# SOM_IO2.net
KiCad netlist of a schematic drawn in Altium Designer
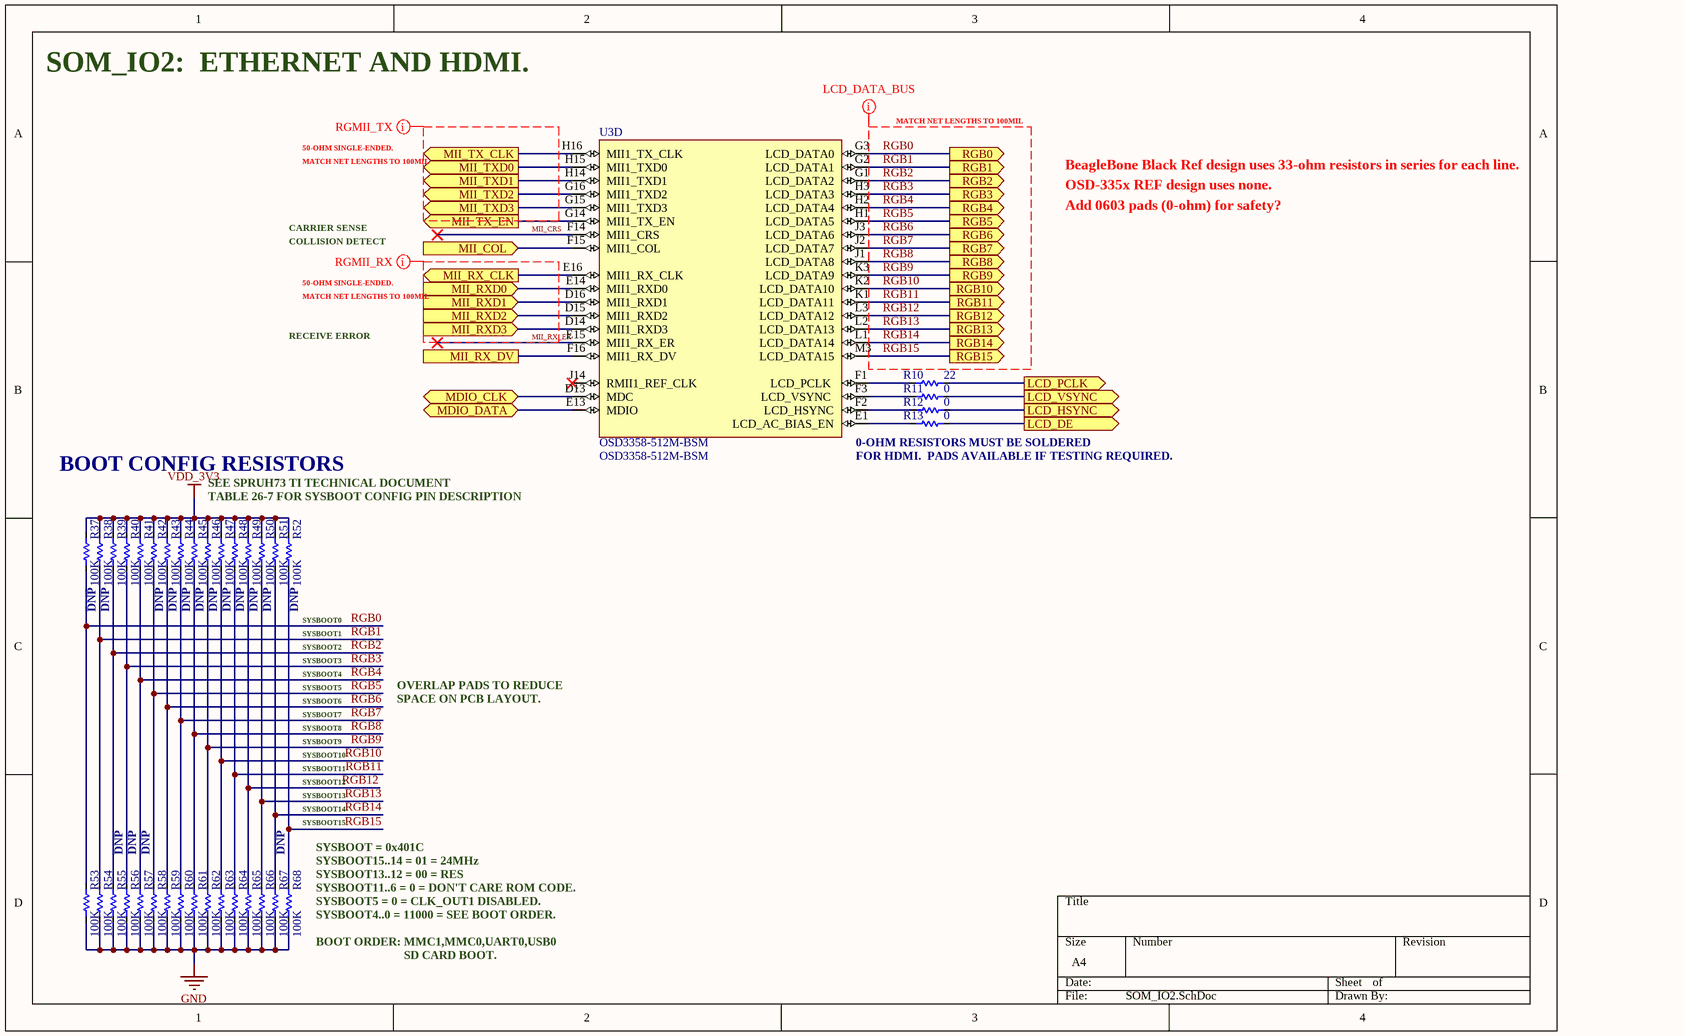
[diagram p0: SOM_IO2.SchDoc]

(export (version "E")
  (design (tool "Eeschema 10.0.6"))
  (components
    (comp (ref "R10")
      (value "22")
      (footprint "RES_0603")
      (description "RES SMD 22 OHM 5% 1/10W 0603")
      (fields (field (name "TOLERANCE") "5%") (field (name "MANUFACTURER") "Yageo"))
      (libsource (lib "OSD335-X_Devboard") (part "RC0603JR-0722RL"))
    )
    (comp (ref "R11")
      (value "0")
      (footprint "RES_0603")
      (description "RES SMD 0 OHM JUMPER 1/10W 0603")
      (fields (field (name "MANUFACTURER") "Yageo") (field (name "MANUFACTURER PART NO.") "RC0603JR-070RL"))
      (libsource (lib "OSD335-X_Devboard") (part "RC0603JR-070RL"))
    )
    (comp (ref "R12")
      (value "0")
      (footprint "RES_0603")
      (description "RES SMD 0 OHM JUMPER 1/10W 0603")
      (fields (field (name "MANUFACTURER") "Yageo") (field (name "MANUFACTURER PART NO.") "RC0603JR-070RL"))
      (libsource (lib "OSD335-X_Devboard") (part "RC0603JR-070RL"))
    )
    (comp (ref "R13")
      (value "0")
      (footprint "RES_0603")
      (description "RES SMD 0 OHM JUMPER 1/10W 0603")
      (fields (field (name "MANUFACTURER") "Yageo") (field (name "MANUFACTURER PART NO.") "RC0603JR-070RL"))
      (libsource (lib "OSD335-X_Devboard") (part "RC0603JR-070RL"))
    )
    (comp (ref "R37")
      (value "100K")
      (footprint "RES_0402")
      (description "RES SMD 100K OHM 1% 1/16W 0402")
      (fields (field (name "TOLERANCE") "1%") (field (name "MANUFACTURER") "Yageo"))
      (libsource (lib "OSD335-X_Devboard") (part "RC0402FR-07100KL"))
    )
    (comp (ref "R38")
      (value "100K")
      (footprint "RES_0402")
      (description "RES SMD 100K OHM 1% 1/16W 0402")
      (fields (field (name "TOLERANCE") "1%") (field (name "MANUFACTURER") "Yageo"))
      (libsource (lib "OSD335-X_Devboard") (part "RC0402FR-07100KL"))
    )
    (comp (ref "R39")
      (value "100K")
      (footprint "RES_0402")
      (description "RES SMD 100K OHM 1% 1/16W 0402")
      (fields (field (name "TOLERANCE") "1%") (field (name "MANUFACTURER") "Yageo"))
      (libsource (lib "OSD335-X_Devboard") (part "RC0402FR-07100KL"))
    )
    (comp (ref "R40")
      (value "100K")
      (footprint "RES_0402")
      (description "RES SMD 100K OHM 1% 1/16W 0402")
      (fields (field (name "TOLERANCE") "1%") (field (name "MANUFACTURER") "Yageo"))
      (libsource (lib "OSD335-X_Devboard") (part "RC0402FR-07100KL"))
    )
    (comp (ref "R41")
      (value "100K")
      (footprint "RES_0402")
      (description "RES SMD 100K OHM 1% 1/16W 0402")
      (fields (field (name "TOLERANCE") "1%") (field (name "MANUFACTURER") "Yageo"))
      (libsource (lib "OSD335-X_Devboard") (part "RC0402FR-07100KL"))
    )
    (comp (ref "R42")
      (value "100K")
      (footprint "RES_0402")
      (description "RES SMD 100K OHM 1% 1/16W 0402")
      (fields (field (name "TOLERANCE") "1%") (field (name "MANUFACTURER") "Yageo"))
      (libsource (lib "OSD335-X_Devboard") (part "RC0402FR-07100KL"))
    )
    (comp (ref "R43")
      (value "100K")
      (footprint "RES_0402")
      (description "RES SMD 100K OHM 1% 1/16W 0402")
      (fields (field (name "TOLERANCE") "1%") (field (name "MANUFACTURER") "Yageo"))
      (libsource (lib "OSD335-X_Devboard") (part "RC0402FR-07100KL"))
    )
    (comp (ref "R44")
      (value "100K")
      (footprint "RES_0402")
      (description "RES SMD 100K OHM 1% 1/16W 0402")
      (fields (field (name "TOLERANCE") "1%") (field (name "MANUFACTURER") "Yageo"))
      (libsource (lib "OSD335-X_Devboard") (part "RC0402FR-07100KL"))
    )
    (comp (ref "R45")
      (value "100K")
      (footprint "RES_0402")
      (description "RES SMD 100K OHM 1% 1/16W 0402")
      (fields (field (name "TOLERANCE") "1%") (field (name "MANUFACTURER") "Yageo"))
      (libsource (lib "OSD335-X_Devboard") (part "RC0402FR-07100KL"))
    )
    (comp (ref "R46")
      (value "100K")
      (footprint "RES_0402")
      (description "RES SMD 100K OHM 1% 1/16W 0402")
      (fields (field (name "TOLERANCE") "1%") (field (name "MANUFACTURER") "Yageo"))
      (libsource (lib "OSD335-X_Devboard") (part "RC0402FR-07100KL"))
    )
    (comp (ref "R47")
      (value "100K")
      (footprint "RES_0402")
      (description "RES SMD 100K OHM 1% 1/16W 0402")
      (fields (field (name "TOLERANCE") "1%") (field (name "MANUFACTURER") "Yageo"))
      (libsource (lib "OSD335-X_Devboard") (part "RC0402FR-07100KL"))
    )
    (comp (ref "R48")
      (value "100K")
      (footprint "RES_0402")
      (description "RES SMD 100K OHM 1% 1/16W 0402")
      (fields (field (name "TOLERANCE") "1%") (field (name "MANUFACTURER") "Yageo"))
      (libsource (lib "OSD335-X_Devboard") (part "RC0402FR-07100KL"))
    )
    (comp (ref "R49")
      (value "100K")
      (footprint "RES_0402")
      (description "RES SMD 100K OHM 1% 1/16W 0402")
      (fields (field (name "TOLERANCE") "1%") (field (name "MANUFACTURER") "Yageo"))
      (libsource (lib "OSD335-X_Devboard") (part "RC0402FR-07100KL"))
    )
    (comp (ref "R50")
      (value "100K")
      (footprint "RES_0402")
      (description "RES SMD 100K OHM 1% 1/16W 0402")
      (fields (field (name "TOLERANCE") "1%") (field (name "MANUFACTURER") "Yageo"))
      (libsource (lib "OSD335-X_Devboard") (part "RC0402FR-07100KL"))
    )
    (comp (ref "R51")
      (value "100K")
      (footprint "RES_0402")
      (description "RES SMD 100K OHM 1% 1/16W 0402")
      (fields (field (name "TOLERANCE") "1%") (field (name "MANUFACTURER") "Yageo"))
      (libsource (lib "OSD335-X_Devboard") (part "RC0402FR-07100KL"))
    )
    (comp (ref "R52")
      (value "100K")
      (footprint "RES_0402")
      (description "RES SMD 100K OHM 1% 1/16W 0402")
      (fields (field (name "TOLERANCE") "1%") (field (name "MANUFACTURER") "Yageo"))
      (libsource (lib "OSD335-X_Devboard") (part "RC0402FR-07100KL"))
    )
    (comp (ref "R53")
      (value "100K")
      (footprint "RES_0402")
      (description "RES SMD 100K OHM 1% 1/16W 0402")
      (fields (field (name "TOLERANCE") "1%") (field (name "MANUFACTURER") "Yageo"))
      (libsource (lib "OSD335-X_Devboard") (part "RC0402FR-07100KL"))
    )
    (comp (ref "R54")
      (value "100K")
      (footprint "RES_0402")
      (description "RES SMD 100K OHM 1% 1/16W 0402")
      (fields (field (name "TOLERANCE") "1%") (field (name "MANUFACTURER") "Yageo"))
      (libsource (lib "OSD335-X_Devboard") (part "RC0402FR-07100KL"))
    )
    (comp (ref "R55")
      (value "100K")
      (footprint "RES_0402")
      (description "RES SMD 100K OHM 1% 1/16W 0402")
      (fields (field (name "TOLERANCE") "1%") (field (name "MANUFACTURER") "Yageo"))
      (libsource (lib "OSD335-X_Devboard") (part "RC0402FR-07100KL"))
    )
    (comp (ref "R56")
      (value "100K")
      (footprint "RES_0402")
      (description "RES SMD 100K OHM 1% 1/16W 0402")
      (fields (field (name "TOLERANCE") "1%") (field (name "MANUFACTURER") "Yageo"))
      (libsource (lib "OSD335-X_Devboard") (part "RC0402FR-07100KL"))
    )
    (comp (ref "R57")
      (value "100K")
      (footprint "RES_0402")
      (description "RES SMD 100K OHM 1% 1/16W 0402")
      (fields (field (name "TOLERANCE") "1%") (field (name "MANUFACTURER") "Yageo"))
      (libsource (lib "OSD335-X_Devboard") (part "RC0402FR-07100KL"))
    )
    (comp (ref "R58")
      (value "100K")
      (footprint "RES_0402")
      (description "RES SMD 100K OHM 1% 1/16W 0402")
      (fields (field (name "TOLERANCE") "1%") (field (name "MANUFACTURER") "Yageo"))
      (libsource (lib "OSD335-X_Devboard") (part "RC0402FR-07100KL"))
    )
    (comp (ref "R59")
      (value "100K")
      (footprint "RES_0402")
      (description "RES SMD 100K OHM 1% 1/16W 0402")
      (fields (field (name "TOLERANCE") "1%") (field (name "MANUFACTURER") "Yageo"))
      (libsource (lib "OSD335-X_Devboard") (part "RC0402FR-07100KL"))
    )
    (comp (ref "R60")
      (value "100K")
      (footprint "RES_0402")
      (description "RES SMD 100K OHM 1% 1/16W 0402")
      (fields (field (name "TOLERANCE") "1%") (field (name "MANUFACTURER") "Yageo"))
      (libsource (lib "OSD335-X_Devboard") (part "RC0402FR-07100KL"))
    )
    (comp (ref "R61")
      (value "100K")
      (footprint "RES_0402")
      (description "RES SMD 100K OHM 1% 1/16W 0402")
      (fields (field (name "TOLERANCE") "1%") (field (name "MANUFACTURER") "Yageo"))
      (libsource (lib "OSD335-X_Devboard") (part "RC0402FR-07100KL"))
    )
    (comp (ref "R62")
      (value "100K")
      (footprint "RES_0402")
      (description "RES SMD 100K OHM 1% 1/16W 0402")
      (fields (field (name "TOLERANCE") "1%") (field (name "MANUFACTURER") "Yageo"))
      (libsource (lib "OSD335-X_Devboard") (part "RC0402FR-07100KL"))
    )
    (comp (ref "R63")
      (value "100K")
      (footprint "RES_0402")
      (description "RES SMD 100K OHM 1% 1/16W 0402")
      (fields (field (name "TOLERANCE") "1%") (field (name "MANUFACTURER") "Yageo"))
      (libsource (lib "OSD335-X_Devboard") (part "RC0402FR-07100KL"))
    )
    (comp (ref "R64")
      (value "100K")
      (footprint "RES_0402")
      (description "RES SMD 100K OHM 1% 1/16W 0402")
      (fields (field (name "TOLERANCE") "1%") (field (name "MANUFACTURER") "Yageo"))
      (libsource (lib "OSD335-X_Devboard") (part "RC0402FR-07100KL"))
    )
    (comp (ref "R65")
      (value "100K")
      (footprint "RES_0402")
      (description "RES SMD 100K OHM 1% 1/16W 0402")
      (fields (field (name "TOLERANCE") "1%") (field (name "MANUFACTURER") "Yageo"))
      (libsource (lib "OSD335-X_Devboard") (part "RC0402FR-07100KL"))
    )
    (comp (ref "R66")
      (value "100K")
      (footprint "RES_0402")
      (description "RES SMD 100K OHM 1% 1/16W 0402")
      (fields (field (name "TOLERANCE") "1%") (field (name "MANUFACTURER") "Yageo"))
      (libsource (lib "OSD335-X_Devboard") (part "RC0402FR-07100KL"))
    )
    (comp (ref "R67")
      (value "100K")
      (footprint "RES_0402")
      (description "RES SMD 100K OHM 1% 1/16W 0402")
      (fields (field (name "TOLERANCE") "1%") (field (name "MANUFACTURER") "Yageo"))
      (libsource (lib "OSD335-X_Devboard") (part "RC0402FR-07100KL"))
    )
    (comp (ref "R68")
      (value "100K")
      (footprint "RES_0402")
      (description "RES SMD 100K OHM 1% 1/16W 0402")
      (fields (field (name "TOLERANCE") "1%") (field (name "MANUFACTURER") "Yageo"))
      (libsource (lib "OSD335-X_Devboard") (part "RC0402FR-07100KL"))
    )
    (comp (ref "U3")
      (value "OSD3358-512M-BSM")
      (footprint "BGA256C127P16X16_2100X2100X308")
      (description "OSD3358-512M-BSM , 256-FBGA, 21mmx21mmx3mm")
      (fields (field (name "MANUFACTURER") "Octavo Systems") (field (name "PARTNUMBER") "OSD3358-512M-BSM"))
      (libsource (lib "OSD335-X_Devboard") (part "SOM-OSD3358-512M-BSM"))
    )
  )
  (nets
    (net (code "1") (name "/LCD_DE") (class "Default")
      (node (ref "R13") (pin "2") (pinfunction "2_2") (pintype "passive"))
    )
    (net (code "2") (name "/LCD_HSYNC") (class "Default")
      (node (ref "R12") (pin "2") (pinfunction "2_2") (pintype "passive"))
    )
    (net (code "3") (name "/LCD_PCLK") (class "Default")
      (node (ref "R10") (pin "2") (pinfunction "2_2") (pintype "passive"))
    )
    (net (code "4") (name "/LCD_VSYNC") (class "Default")
      (node (ref "R11") (pin "2") (pinfunction "2_2") (pintype "passive"))
    )
    (net (code "5") (name "/MDIO_CLK") (class "Default")
      (node (ref "U3") (pin "D13") (pinfunction "MDC_D13") (pintype "bidirectional"))
    )
    (net (code "6") (name "/MDIO_DATA") (class "Default")
      (node (ref "U3") (pin "E13") (pinfunction "MDIO_E13") (pintype "bidirectional"))
    )
    (net (code "7") (name "/MII_COL") (class "Default")
      (node (ref "U3") (pin "F15") (pinfunction "MII1_COL_F15") (pintype "bidirectional"))
    )
    (net (code "8") (name "/MII_CRS") (class "Default")
      (node (ref "U3") (pin "F14") (pinfunction "MII1_CRS_F14") (pintype "bidirectional+no_connect"))
    )
    (net (code "9") (name "/MII_RXD0") (class "Default")
      (node (ref "U3") (pin "E14") (pinfunction "MII1_RXD0_E14") (pintype "bidirectional"))
    )
    (net (code "10") (name "/MII_RXD1") (class "Default")
      (node (ref "U3") (pin "D16") (pinfunction "MII1_RXD1_D16") (pintype "bidirectional"))
    )
    (net (code "11") (name "/MII_RXD2") (class "Default")
      (node (ref "U3") (pin "D15") (pinfunction "MII1_RXD2_D15") (pintype "bidirectional"))
    )
    (net (code "12") (name "/MII_RXD3") (class "Default")
      (node (ref "U3") (pin "D14") (pinfunction "MII1_RXD3_D14") (pintype "bidirectional"))
    )
    (net (code "13") (name "/MII_RX_CLK") (class "Default")
      (node (ref "U3") (pin "E16") (pinfunction "MII1_RX_CLK_E16") (pintype "bidirectional"))
    )
    (net (code "14") (name "/MII_RX_DV") (class "Default")
      (node (ref "U3") (pin "F16") (pinfunction "MII1_RX_DV_F16") (pintype "bidirectional"))
    )
    (net (code "15") (name "/MII_RX_ER") (class "Default")
      (node (ref "U3") (pin "E15") (pinfunction "MII1_RX_ER_E15") (pintype "bidirectional+no_connect"))
    )
    (net (code "16") (name "/MII_TXD0") (class "Default")
      (node (ref "U3") (pin "H15") (pinfunction "MII1_TXD0_H15") (pintype "bidirectional"))
    )
    (net (code "17") (name "/MII_TXD1") (class "Default")
      (node (ref "U3") (pin "H14") (pinfunction "MII1_TXD1_H14") (pintype "bidirectional"))
    )
    (net (code "18") (name "/MII_TXD2") (class "Default")
      (node (ref "U3") (pin "G16") (pinfunction "MII1_TXD2_G16") (pintype "bidirectional"))
    )
    (net (code "19") (name "/MII_TXD3") (class "Default")
      (node (ref "U3") (pin "G15") (pinfunction "MII1_TXD3_G15") (pintype "bidirectional"))
    )
    (net (code "20") (name "/MII_TX_CLK") (class "Default")
      (node (ref "U3") (pin "H16") (pinfunction "MII1_TX_CLK_H16") (pintype "bidirectional"))
    )
    (net (code "21") (name "/MII_TX_EN") (class "Default")
      (node (ref "U3") (pin "G14") (pinfunction "MII1_TX_EN_G14") (pintype "bidirectional"))
    )
    (net (code "22") (name "/RGB0") (class "Default")
      (node (ref "R37") (pin "1") (pinfunction "1_1") (pintype "passive"))
      (node (ref "R53") (pin "2") (pinfunction "2_2") (pintype "passive"))
      (node (ref "U3") (pin "G3") (pinfunction "LCD_DATA0_G3") (pintype "bidirectional"))
    )
    (net (code "23") (name "/RGB1") (class "Default")
      (node (ref "R38") (pin "1") (pinfunction "1_1") (pintype "passive"))
      (node (ref "R54") (pin "2") (pinfunction "2_2") (pintype "passive"))
      (node (ref "U3") (pin "G2") (pinfunction "LCD_DATA1_G2") (pintype "bidirectional"))
    )
    (net (code "24") (name "/RGB2") (class "Default")
      (node (ref "R39") (pin "1") (pinfunction "1_1") (pintype "passive"))
      (node (ref "R55") (pin "2") (pinfunction "2_2") (pintype "passive"))
      (node (ref "U3") (pin "G1") (pinfunction "LCD_DATA2_G1") (pintype "bidirectional"))
    )
    (net (code "25") (name "/RGB3") (class "Default")
      (node (ref "R40") (pin "1") (pinfunction "1_1") (pintype "passive"))
      (node (ref "R56") (pin "2") (pinfunction "2_2") (pintype "passive"))
      (node (ref "U3") (pin "H3") (pinfunction "LCD_DATA3_H3") (pintype "bidirectional"))
    )
    (net (code "26") (name "/RGB4") (class "Default")
      (node (ref "R41") (pin "1") (pinfunction "1_1") (pintype "passive"))
      (node (ref "R57") (pin "2") (pinfunction "2_2") (pintype "passive"))
      (node (ref "U3") (pin "H2") (pinfunction "LCD_DATA4_H2") (pintype "bidirectional"))
    )
    (net (code "27") (name "/RGB5") (class "Default")
      (node (ref "R42") (pin "1") (pinfunction "1_1") (pintype "passive"))
      (node (ref "R58") (pin "2") (pinfunction "2_2") (pintype "passive"))
      (node (ref "U3") (pin "H1") (pinfunction "LCD_DATA5_H1") (pintype "bidirectional"))
    )
    (net (code "28") (name "/RGB6") (class "Default")
      (node (ref "R43") (pin "1") (pinfunction "1_1") (pintype "passive"))
      (node (ref "R59") (pin "2") (pinfunction "2_2") (pintype "passive"))
      (node (ref "U3") (pin "J3") (pinfunction "LCD_DATA6_J3") (pintype "bidirectional"))
    )
    (net (code "29") (name "/RGB7") (class "Default")
      (node (ref "R44") (pin "1") (pinfunction "1_1") (pintype "passive"))
      (node (ref "R60") (pin "2") (pinfunction "2_2") (pintype "passive"))
      (node (ref "U3") (pin "J2") (pinfunction "LCD_DATA7_J2") (pintype "bidirectional"))
    )
    (net (code "30") (name "/RGB8") (class "Default")
      (node (ref "R45") (pin "1") (pinfunction "1_1") (pintype "passive"))
      (node (ref "R61") (pin "2") (pinfunction "2_2") (pintype "passive"))
      (node (ref "U3") (pin "J1") (pinfunction "LCD_DATA8_J1") (pintype "bidirectional"))
    )
    (net (code "31") (name "/RGB9") (class "Default")
      (node (ref "R46") (pin "1") (pinfunction "1_1") (pintype "passive"))
      (node (ref "R62") (pin "2") (pinfunction "2_2") (pintype "passive"))
      (node (ref "U3") (pin "K3") (pinfunction "LCD_DATA9_K3") (pintype "bidirectional"))
    )
    (net (code "32") (name "/RGB10") (class "Default")
      (node (ref "R47") (pin "1") (pinfunction "1_1") (pintype "passive"))
      (node (ref "R63") (pin "2") (pinfunction "2_2") (pintype "passive"))
      (node (ref "U3") (pin "K2") (pinfunction "LCD_DATA10_K2") (pintype "bidirectional"))
    )
    (net (code "33") (name "/RGB11") (class "Default")
      (node (ref "R48") (pin "1") (pinfunction "1_1") (pintype "passive"))
      (node (ref "R64") (pin "2") (pinfunction "2_2") (pintype "passive"))
      (node (ref "U3") (pin "K1") (pinfunction "LCD_DATA11_K1") (pintype "bidirectional"))
    )
    (net (code "34") (name "/RGB12") (class "Default")
      (node (ref "R49") (pin "1") (pinfunction "1_1") (pintype "passive"))
      (node (ref "R65") (pin "2") (pinfunction "2_2") (pintype "passive"))
      (node (ref "U3") (pin "L3") (pinfunction "LCD_DATA12_L3") (pintype "bidirectional"))
    )
    (net (code "35") (name "/RGB13") (class "Default")
      (node (ref "R50") (pin "1") (pinfunction "1_1") (pintype "passive"))
      (node (ref "R66") (pin "2") (pinfunction "2_2") (pintype "passive"))
      (node (ref "U3") (pin "L2") (pinfunction "LCD_DATA13_L2") (pintype "bidirectional"))
    )
    (net (code "36") (name "/RGB14") (class "Default")
      (node (ref "R51") (pin "1") (pinfunction "1_1") (pintype "passive"))
      (node (ref "R67") (pin "2") (pinfunction "2_2") (pintype "passive"))
      (node (ref "U3") (pin "L1") (pinfunction "LCD_DATA14_L1") (pintype "bidirectional"))
    )
    (net (code "37") (name "/RGB15") (class "Default")
      (node (ref "R52") (pin "1") (pinfunction "1_1") (pintype "passive"))
      (node (ref "R68") (pin "2") (pinfunction "2_2") (pintype "passive"))
      (node (ref "U3") (pin "M3") (pinfunction "LCD_DATA15_M3") (pintype "bidirectional"))
    )
    (net (code "38") (name "GND") (class "Default")
      (node (ref "R53") (pin "1") (pinfunction "1_1") (pintype "passive"))
      (node (ref "R54") (pin "1") (pinfunction "1_1") (pintype "passive"))
      (node (ref "R55") (pin "1") (pinfunction "1_1") (pintype "passive"))
      (node (ref "R56") (pin "1") (pinfunction "1_1") (pintype "passive"))
      (node (ref "R57") (pin "1") (pinfunction "1_1") (pintype "passive"))
      (node (ref "R58") (pin "1") (pinfunction "1_1") (pintype "passive"))
      (node (ref "R59") (pin "1") (pinfunction "1_1") (pintype "passive"))
      (node (ref "R60") (pin "1") (pinfunction "1_1") (pintype "passive"))
      (node (ref "R61") (pin "1") (pinfunction "1_1") (pintype "passive"))
      (node (ref "R62") (pin "1") (pinfunction "1_1") (pintype "passive"))
      (node (ref "R63") (pin "1") (pinfunction "1_1") (pintype "passive"))
      (node (ref "R64") (pin "1") (pinfunction "1_1") (pintype "passive"))
      (node (ref "R65") (pin "1") (pinfunction "1_1") (pintype "passive"))
      (node (ref "R66") (pin "1") (pinfunction "1_1") (pintype "passive"))
      (node (ref "R67") (pin "1") (pinfunction "1_1") (pintype "passive"))
      (node (ref "R68") (pin "1") (pinfunction "1_1") (pintype "passive"))
    )
    (net (code "39") (name "Net-(U3D-LCD_AC_BIAS_EN)") (class "Default")
      (node (ref "R13") (pin "1") (pinfunction "1_1") (pintype "passive"))
      (node (ref "U3") (pin "E1") (pinfunction "LCD_AC_BIAS_EN_E1") (pintype "bidirectional"))
    )
    (net (code "40") (name "Net-(U3D-LCD_HSYNC)") (class "Default")
      (node (ref "R12") (pin "1") (pinfunction "1_1") (pintype "passive"))
      (node (ref "U3") (pin "F2") (pinfunction "LCD_HSYNC_F2") (pintype "bidirectional"))
    )
    (net (code "41") (name "Net-(U3D-LCD_PCLK)") (class "Default")
      (node (ref "R10") (pin "1") (pinfunction "1_1") (pintype "passive"))
      (node (ref "U3") (pin "F1") (pinfunction "LCD_PCLK_F1") (pintype "bidirectional"))
    )
    (net (code "42") (name "Net-(U3D-LCD_VSYNC)") (class "Default")
      (node (ref "R11") (pin "1") (pinfunction "1_1") (pintype "passive"))
      (node (ref "U3") (pin "F3") (pinfunction "LCD_VSYNC_F3") (pintype "bidirectional"))
    )
    (net (code "43") (name "VDD_3V3") (class "Default")
      (node (ref "R37") (pin "2") (pinfunction "2_2") (pintype "passive"))
      (node (ref "R38") (pin "2") (pinfunction "2_2") (pintype "passive"))
      (node (ref "R39") (pin "2") (pinfunction "2_2") (pintype "passive"))
      (node (ref "R40") (pin "2") (pinfunction "2_2") (pintype "passive"))
      (node (ref "R41") (pin "2") (pinfunction "2_2") (pintype "passive"))
      (node (ref "R42") (pin "2") (pinfunction "2_2") (pintype "passive"))
      (node (ref "R43") (pin "2") (pinfunction "2_2") (pintype "passive"))
      (node (ref "R44") (pin "2") (pinfunction "2_2") (pintype "passive"))
      (node (ref "R45") (pin "2") (pinfunction "2_2") (pintype "passive"))
      (node (ref "R46") (pin "2") (pinfunction "2_2") (pintype "passive"))
      (node (ref "R47") (pin "2") (pinfunction "2_2") (pintype "passive"))
      (node (ref "R48") (pin "2") (pinfunction "2_2") (pintype "passive"))
      (node (ref "R49") (pin "2") (pinfunction "2_2") (pintype "passive"))
      (node (ref "R50") (pin "2") (pinfunction "2_2") (pintype "passive"))
      (node (ref "R51") (pin "2") (pinfunction "2_2") (pintype "passive"))
      (node (ref "R52") (pin "2") (pinfunction "2_2") (pintype "passive"))
    )
    (net (code "44") (name "unconnected-(U3D-RMII1_REF_CLK-PadJ14)") (class "Default")
      (node (ref "U3") (pin "J14") (pinfunction "RMII1_REF_CLK_J14") (pintype "bidirectional+no_connect"))
    )
  )
)
